# VCOBoardTrimCap.net
KiCad netlist of a schematic drawn in EAGLE
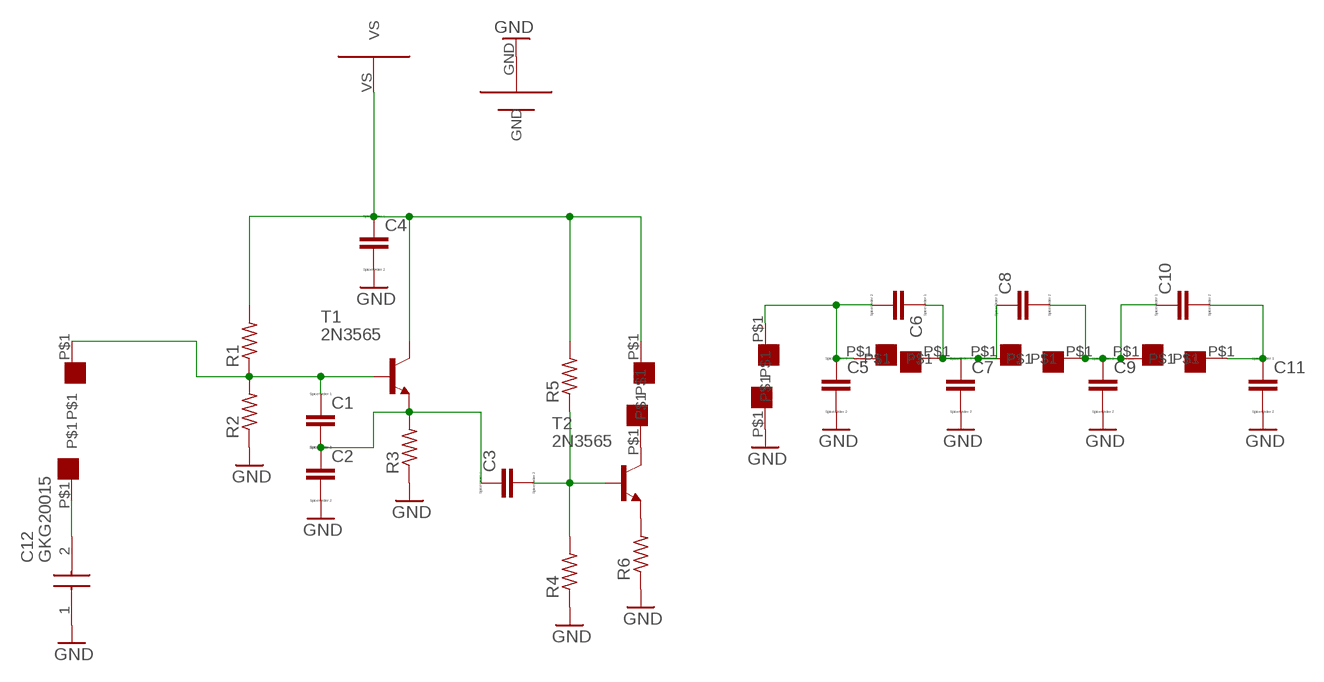
[diagram p0: schematic, sheet 1]

(export (version "E")
  (design (tool "Eeschema 10.0.6"))
  (components
    (comp (ref "C1") (value "C") (footprint "eagle-import:C0805") (libsource (lib "eagle-import") (part "C")))
    (comp (ref "C2") (value "C") (footprint "eagle-import:C0805") (libsource (lib "eagle-import") (part "C")))
    (comp (ref "C3") (value "C") (footprint "eagle-import:C0805") (libsource (lib "eagle-import") (part "C")))
    (comp (ref "C4") (value "C") (footprint "eagle-import:C0805") (libsource (lib "eagle-import") (part "C")))
    (comp (ref "C5") (value "C") (footprint "eagle-import:C0805") (libsource (lib "eagle-import") (part "C")))
    (comp (ref "C6") (value "C") (footprint "eagle-import:C0805") (libsource (lib "eagle-import") (part "C")))
    (comp (ref "C7") (value "C") (footprint "eagle-import:C0805") (libsource (lib "eagle-import") (part "C")))
    (comp (ref "C8") (value "C") (footprint "eagle-import:C0805") (libsource (lib "eagle-import") (part "C")))
    (comp (ref "C9") (value "C") (footprint "eagle-import:C0805") (libsource (lib "eagle-import") (part "C")))
    (comp (ref "C10")
      (value "C")
      (footprint "eagle-import:C0805")
      (libsource (lib "eagle-import") (part "C"))
    )
    (comp (ref "C11")
      (value "C")
      (footprint "eagle-import:C0805")
      (libsource (lib "eagle-import") (part "C"))
    )
    (comp (ref "C12")
      (value "GKG20015")
      (footprint "eagle-import:GKG20015")
      (fields (field (name "MOUSER_PART_NUMBER") "659-GKG20015"))
      (libsource (lib "eagle-import") (part "GKG20015"))
    )
    (comp (ref "R1")
      (value "R-US_R0805")
      (footprint "eagle-import:R0805")
      (libsource (lib "eagle-import") (part "R-US_R0805"))
    )
    (comp (ref "R2")
      (value "R-US_R0805")
      (footprint "eagle-import:R0805")
      (libsource (lib "eagle-import") (part "R-US_R0805"))
    )
    (comp (ref "R3")
      (value "R-US_R0805")
      (footprint "eagle-import:R0805")
      (libsource (lib "eagle-import") (part "R-US_R0805"))
    )
    (comp (ref "R4")
      (value "R-US_R0805")
      (footprint "eagle-import:R0805")
      (libsource (lib "eagle-import") (part "R-US_R0805"))
    )
    (comp (ref "R5")
      (value "R-US_R0805")
      (footprint "eagle-import:R0805")
      (libsource (lib "eagle-import") (part "R-US_R0805"))
    )
    (comp (ref "R6")
      (value "R-US_R0805")
      (footprint "eagle-import:R0805")
      (libsource (lib "eagle-import") (part "R-US_R0805"))
    )
    (comp (ref "T1")
      (value "2N3565")
      (footprint "eagle-import:TO92")
      (libsource (lib "eagle-import") (part "2N3565"))
    )
    (comp (ref "T2")
      (value "2N3565")
      (footprint "eagle-import:TO92")
      (libsource (lib "eagle-import") (part "2N3565"))
    )
    (comp (ref "U$1")
      (value "PAD")
      (footprint "eagle-import:PAD")
      (libsource (lib "eagle-import") (part "PAD"))
    )
    (comp (ref "U$2")
      (value "PAD")
      (footprint "eagle-import:PAD")
      (libsource (lib "eagle-import") (part "PAD"))
    )
    (comp (ref "U$3")
      (value "PAD")
      (footprint "eagle-import:PAD")
      (libsource (lib "eagle-import") (part "PAD"))
    )
    (comp (ref "U$4")
      (value "PAD")
      (footprint "eagle-import:PAD")
      (libsource (lib "eagle-import") (part "PAD"))
    )
    (comp (ref "U$5")
      (value "ALLIGATORCLIPS")
      (footprint "eagle-import:ALLIGATORCONNECTOR")
      (libsource (lib "eagle-import") (part "ALLIGATORCLIPS"))
    )
    (comp (ref "U$6")
      (value "PAD")
      (footprint "eagle-import:PAD")
      (libsource (lib "eagle-import") (part "PAD"))
    )
    (comp (ref "U$7")
      (value "PAD")
      (footprint "eagle-import:PAD")
      (libsource (lib "eagle-import") (part "PAD"))
    )
    (comp (ref "U$8")
      (value "PAD")
      (footprint "eagle-import:PAD")
      (libsource (lib "eagle-import") (part "PAD"))
    )
    (comp (ref "U$9")
      (value "PAD")
      (footprint "eagle-import:PAD")
      (libsource (lib "eagle-import") (part "PAD"))
    )
    (comp (ref "U$10")
      (value "PAD")
      (footprint "eagle-import:PAD")
      (libsource (lib "eagle-import") (part "PAD"))
    )
    (comp (ref "U$11")
      (value "PAD")
      (footprint "eagle-import:PAD")
      (libsource (lib "eagle-import") (part "PAD"))
    )
    (comp (ref "U$12")
      (value "PAD")
      (footprint "eagle-import:PAD")
      (libsource (lib "eagle-import") (part "PAD"))
    )
    (comp (ref "U$13")
      (value "PAD")
      (footprint "eagle-import:PAD")
      (libsource (lib "eagle-import") (part "PAD"))
    )
  )
  (nets
    (net (code "1") (name "GND") (class "Default")
      (node (ref "C11") (pin "2") (pinfunction "2_2") (pintype "passive"))
      (node (ref "C12") (pin "1") (pinfunction "1_1") (pintype "bidirectional"))
      (node (ref "C2") (pin "2") (pinfunction "2_2") (pintype "passive"))
      (node (ref "C4") (pin "2") (pinfunction "2_2") (pintype "passive"))
      (node (ref "C5") (pin "2") (pinfunction "2_2") (pintype "passive"))
      (node (ref "C7") (pin "2") (pinfunction "2_2") (pintype "passive"))
      (node (ref "C9") (pin "2") (pinfunction "2_2") (pintype "passive"))
      (node (ref "R2") (pin "1") (pinfunction "1_1") (pintype "passive"))
      (node (ref "R3") (pin "1") (pinfunction "1_1") (pintype "passive"))
      (node (ref "R4") (pin "1") (pinfunction "1_1") (pintype "passive"))
      (node (ref "R6") (pin "1") (pinfunction "1_1") (pintype "passive"))
      (node (ref "U$4") (pin "P$1") (pinfunction "P$1_P$1") (pintype "bidirectional"))
      (node (ref "U$5") (pin "GND") (pinfunction "GND_GND") (pintype "bidirectional"))
    )
    (net (code "2") (name "Net-(C5-Pad1)") (class "Default")
      (node (ref "C5") (pin "1") (pinfunction "1_1") (pintype "passive"))
      (node (ref "C6") (pin "2") (pinfunction "2_2") (pintype "passive"))
      (node (ref "U$3") (pin "P$1") (pinfunction "P$1_P$1") (pintype "bidirectional"))
      (node (ref "U$8") (pin "P$1") (pinfunction "P$1_P$1") (pintype "bidirectional"))
    )
    (net (code "3") (name "Net-(C6-Pad1)") (class "Default")
      (node (ref "C6") (pin "1") (pinfunction "1_1") (pintype "passive"))
      (node (ref "C7") (pin "1") (pinfunction "1_1") (pintype "passive"))
      (node (ref "C8") (pin "1") (pinfunction "1_1") (pintype "passive"))
      (node (ref "U$10") (pin "P$1") (pinfunction "P$1_P$1") (pintype "bidirectional"))
      (node (ref "U$9") (pin "P$1") (pinfunction "P$1_P$1") (pintype "bidirectional"))
    )
    (net (code "4") (name "Net-(C10-Pad1)") (class "Default")
      (node (ref "C10") (pin "1") (pinfunction "1_1") (pintype "passive"))
      (node (ref "C8") (pin "2") (pinfunction "2_2") (pintype "passive"))
      (node (ref "C9") (pin "1") (pinfunction "1_1") (pintype "passive"))
      (node (ref "U$11") (pin "P$1") (pinfunction "P$1_P$1") (pintype "bidirectional"))
      (node (ref "U$12") (pin "P$1") (pinfunction "P$1_P$1") (pintype "bidirectional"))
    )
    (net (code "5") (name "Net-(C10-Pad2)") (class "Default")
      (node (ref "C10") (pin "2") (pinfunction "2_2") (pintype "passive"))
      (node (ref "C11") (pin "1") (pinfunction "1_1") (pintype "passive"))
      (node (ref "U$13") (pin "P$1") (pinfunction "P$1_P$1") (pintype "bidirectional"))
    )
    (net (code "6") (name "Net-(C12-Pad2)") (class "Default")
      (node (ref "C12") (pin "2") (pinfunction "2_2") (pintype "bidirectional"))
      (node (ref "U$6") (pin "P$1") (pinfunction "P$1_P$1") (pintype "bidirectional"))
    )
    (net (code "7") (name "Net-(T1-B)") (class "Default")
      (node (ref "C1") (pin "1") (pinfunction "1_1") (pintype "passive"))
      (node (ref "R1") (pin "1") (pinfunction "1_1") (pintype "passive"))
      (node (ref "R2") (pin "2") (pinfunction "2_2") (pintype "passive"))
      (node (ref "T1") (pin "2") (pinfunction "B_2") (pintype "passive"))
      (node (ref "U$7") (pin "P$1") (pinfunction "P$1_P$1") (pintype "bidirectional"))
    )
    (net (code "8") (name "Net-(T1-C)") (class "Default")
      (node (ref "C4") (pin "1") (pinfunction "1_1") (pintype "passive"))
      (node (ref "R1") (pin "2") (pinfunction "2_2") (pintype "passive"))
      (node (ref "R5") (pin "2") (pinfunction "2_2") (pintype "passive"))
      (node (ref "T1") (pin "1") (pinfunction "C_1") (pintype "passive"))
      (node (ref "U$2") (pin "P$1") (pinfunction "P$1_P$1") (pintype "bidirectional"))
      (node (ref "U$5") (pin "VS") (pinfunction "VS_VS") (pintype "bidirectional"))
    )
    (net (code "9") (name "Net-(T1-E)") (class "Default")
      (node (ref "C1") (pin "2") (pinfunction "2_2") (pintype "passive"))
      (node (ref "C2") (pin "1") (pinfunction "1_1") (pintype "passive"))
      (node (ref "C3") (pin "1") (pinfunction "1_1") (pintype "passive"))
      (node (ref "R3") (pin "2") (pinfunction "2_2") (pintype "passive"))
      (node (ref "T1") (pin "3") (pinfunction "E_3") (pintype "passive"))
    )
    (net (code "10") (name "Net-(T2-B)") (class "Default")
      (node (ref "C3") (pin "2") (pinfunction "2_2") (pintype "passive"))
      (node (ref "R4") (pin "2") (pinfunction "2_2") (pintype "passive"))
      (node (ref "R5") (pin "1") (pinfunction "1_1") (pintype "passive"))
      (node (ref "T2") (pin "2") (pinfunction "B_2") (pintype "passive"))
    )
    (net (code "11") (name "Net-(T2-C)") (class "Default")
      (node (ref "T2") (pin "1") (pinfunction "C_1") (pintype "passive"))
      (node (ref "U$1") (pin "P$1") (pinfunction "P$1_P$1") (pintype "bidirectional"))
    )
    (net (code "12") (name "Net-(T2-E)") (class "Default")
      (node (ref "R6") (pin "2") (pinfunction "2_2") (pintype "passive"))
      (node (ref "T2") (pin "3") (pinfunction "E_3") (pintype "passive"))
    )
  )
)
